# ESP32_schematic1.net
KiCad netlist of a schematic drawn in Altium Designer
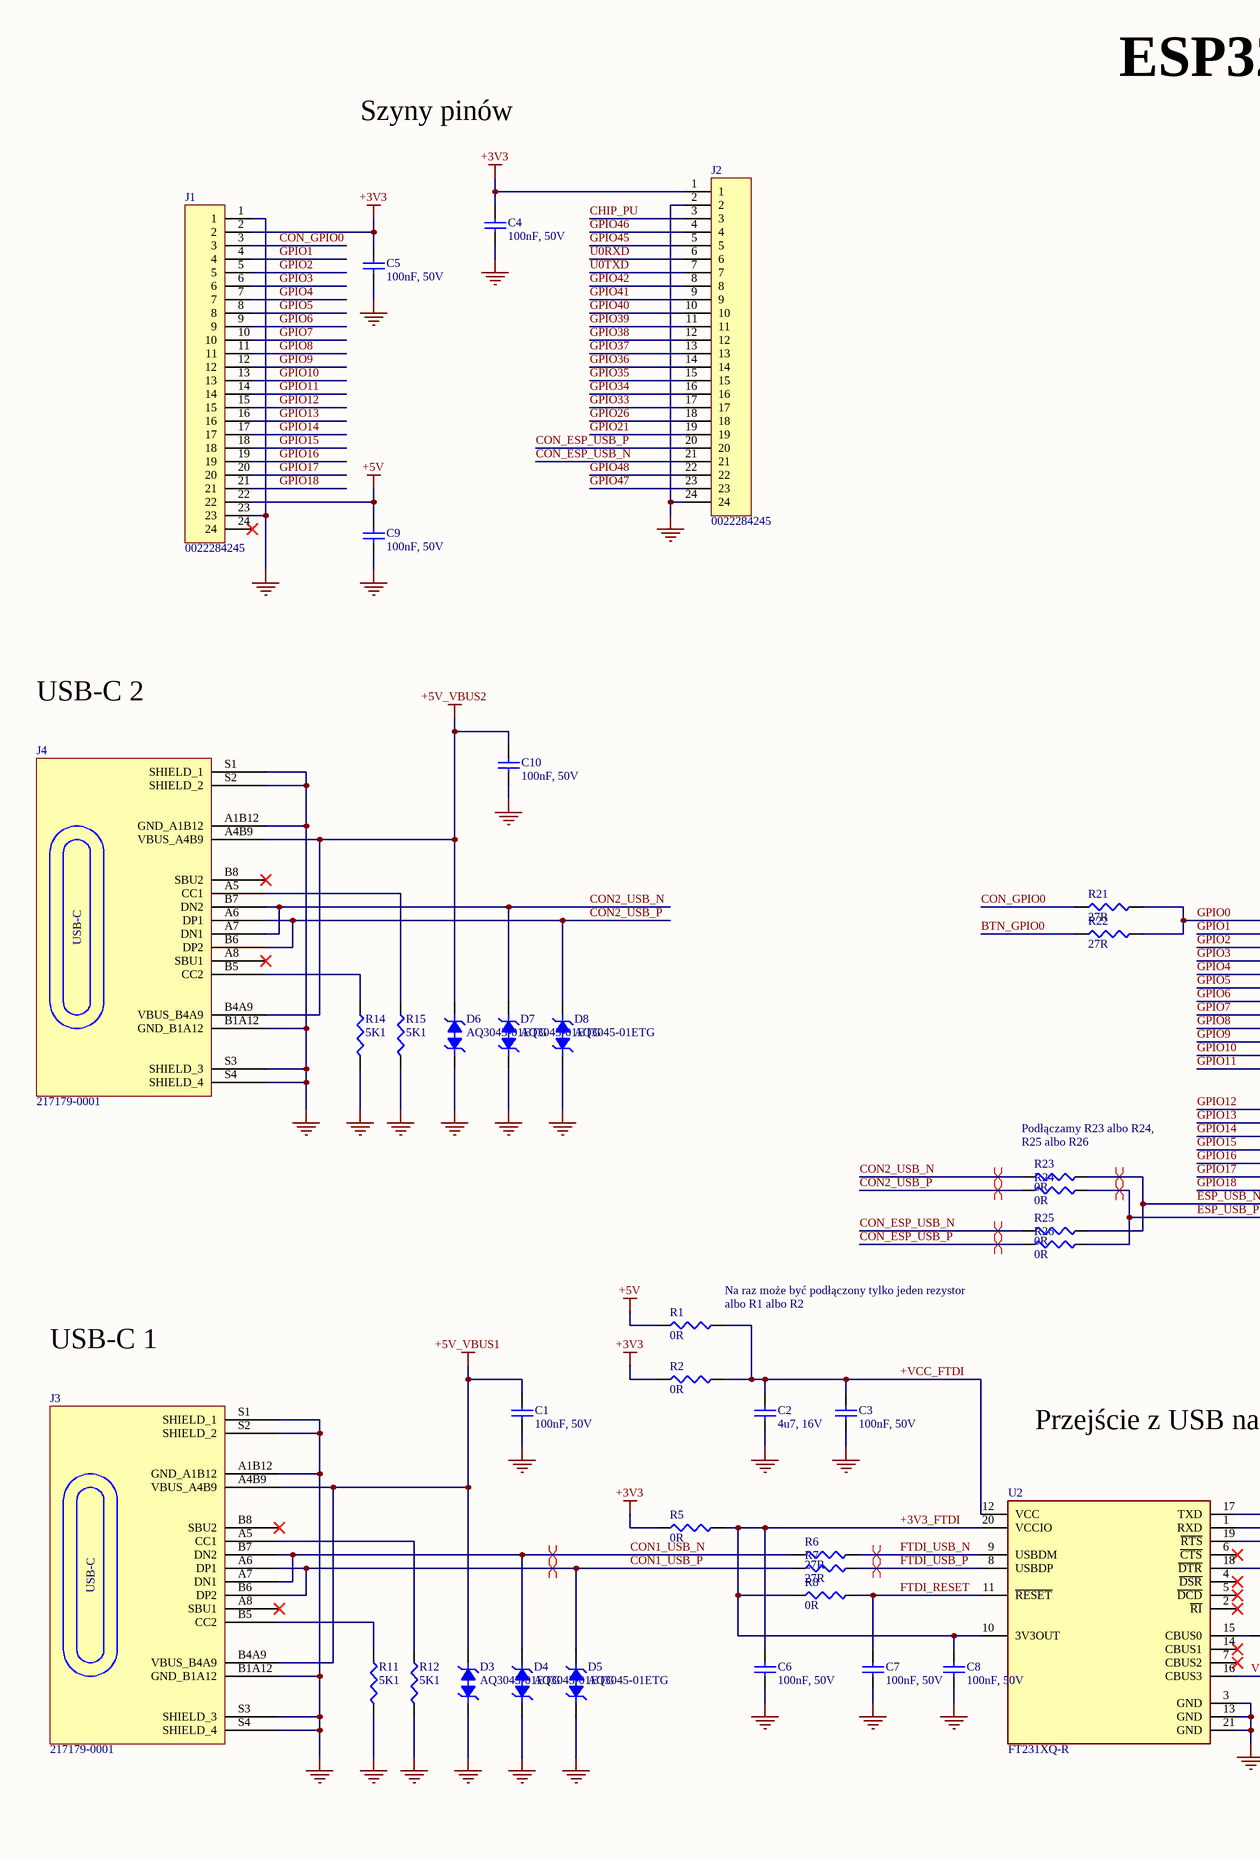
[diagram p0: ESP32_schematic1.SchDoc, left]
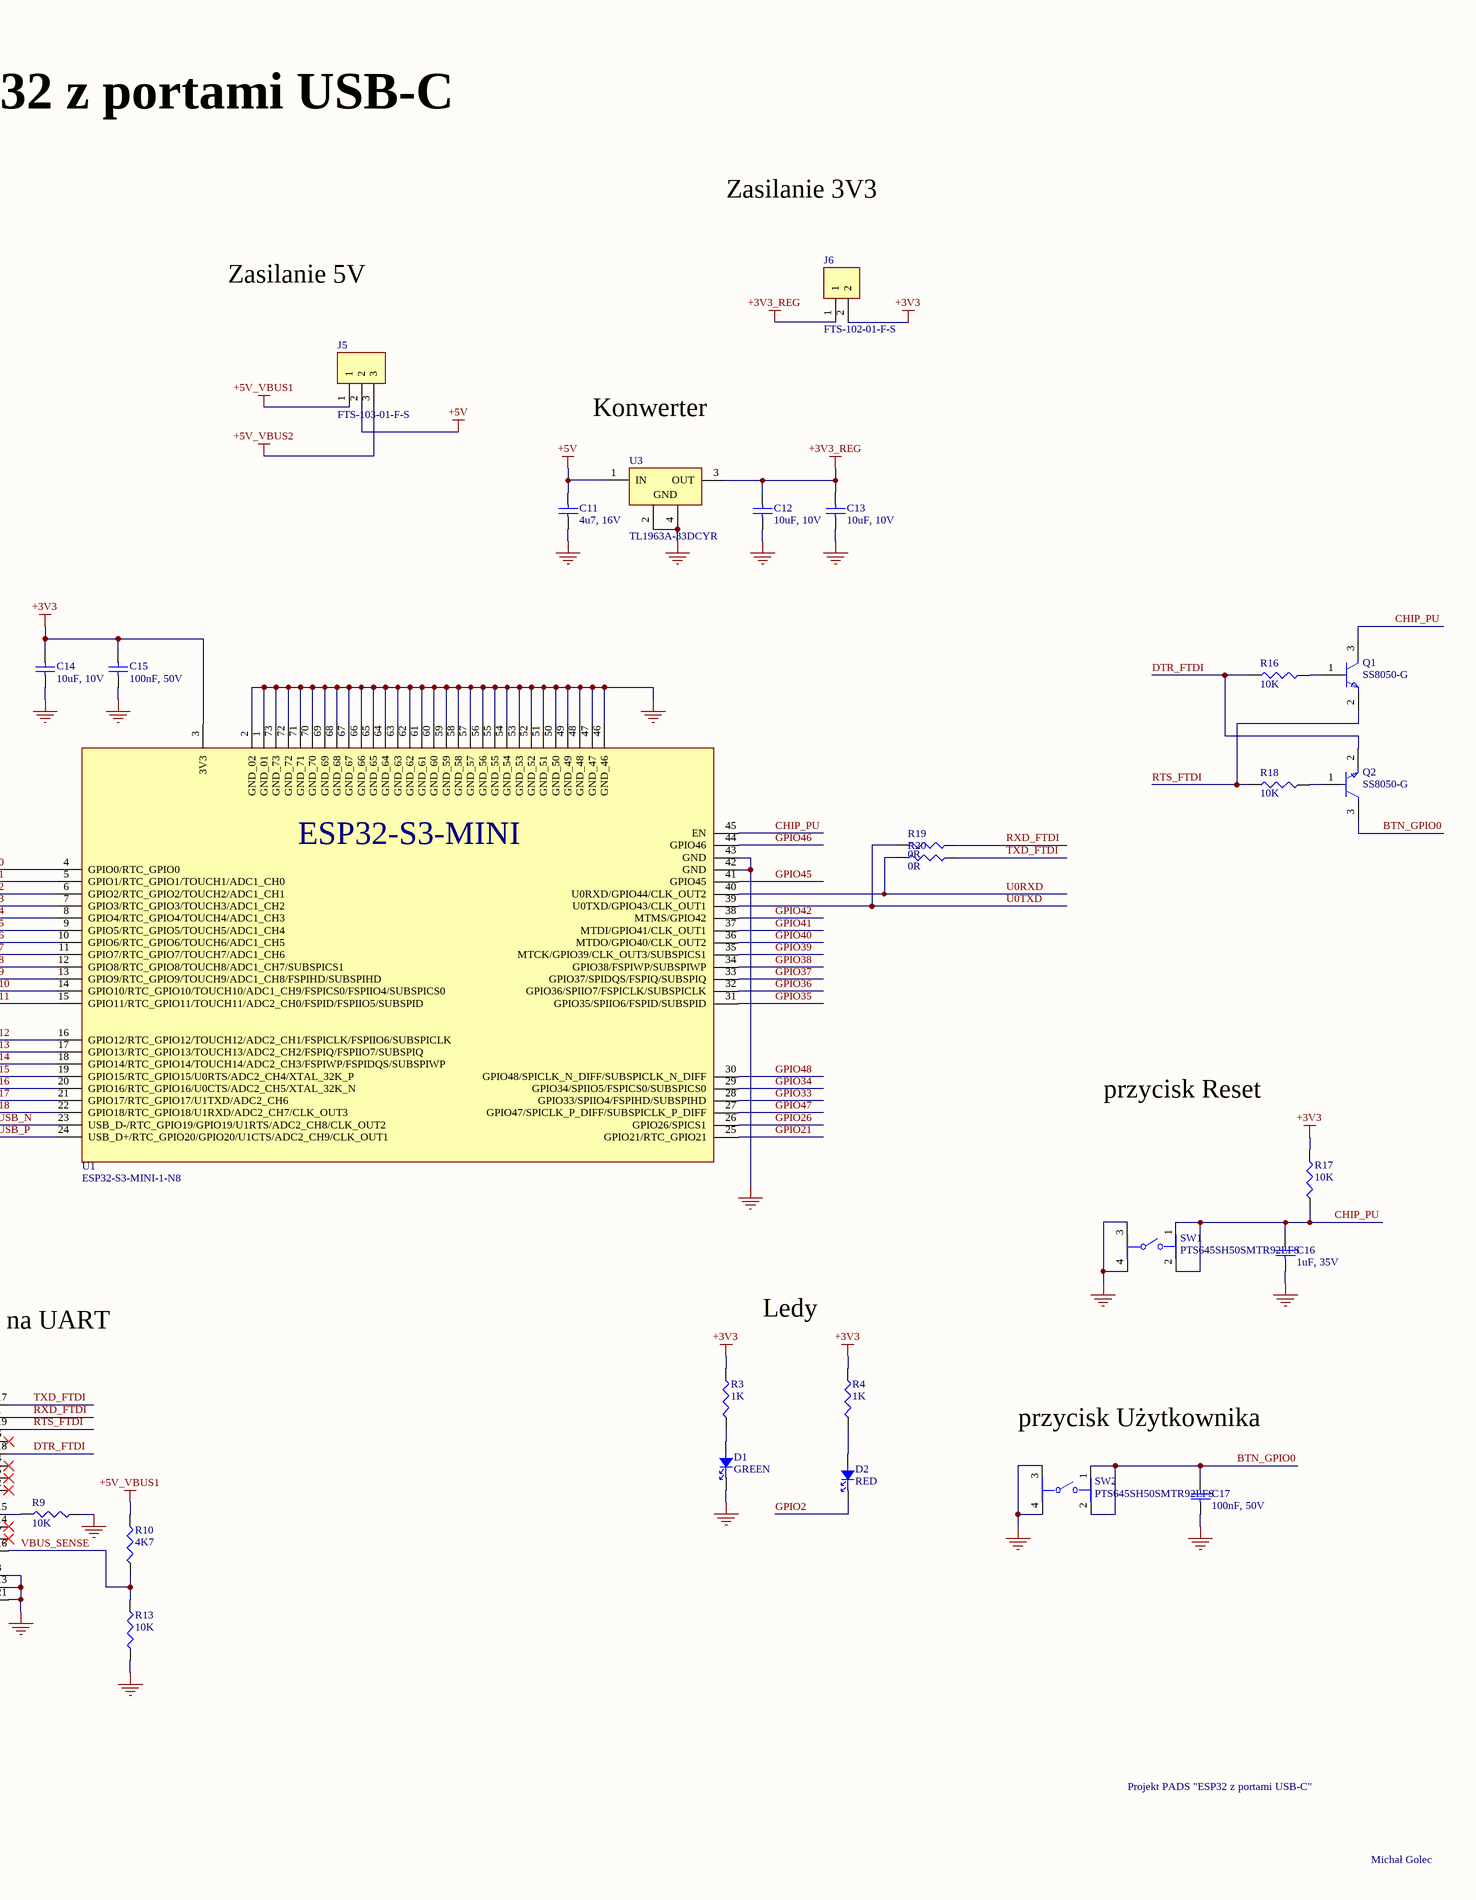
[diagram p1: ESP32_schematic1.SchDoc, right]

(export (version "E")
  (design (tool "Eeschema 10.0.6"))
  (components
    (comp (ref "C1")
      (value "100nF, 50V")
      (footprint "CAPC1005X55N")
      (description "CAP CER 0.1UF 50V X7R 0402")
      (fields
        (field (name "MANUFACTURER") "Samsung")
        (field (name "MANUFACTURER PART NUMBER") "CL05B104KB54PNC")
      )
      (libsource (lib "Schlib") (part "CL05B104KB54PNC"))
    )
    (comp (ref "C2")
      (value "4u7, 16V")
      (footprint "CAPC1005X55N")
      (description "CAP CER 4.7UF 16V X5R 0402")
      (fields
        (field (name "MANUFACTURER") "Samsung")
        (field (name "MANUFACTURER PART NUMBER") "CL05A475MO5NUNC")
      )
      (libsource (lib "Schlib") (part "CL05A475MO5NUNC"))
    )
    (comp (ref "C3")
      (value "100nF, 50V")
      (footprint "CAPC1005X55N")
      (description "CAP CER 0.1UF 50V X7R 0402")
      (fields
        (field (name "MANUFACTURER") "Samsung")
        (field (name "MANUFACTURER PART NUMBER") "CL05B104KB54PNC")
      )
      (libsource (lib "Schlib") (part "CL05B104KB54PNC"))
    )
    (comp (ref "C4")
      (value "100nF, 50V")
      (footprint "CAPC1005X55N")
      (description "CAP CER 0.1UF 50V X7R 0402")
      (fields
        (field (name "MANUFACTURER") "Samsung")
        (field (name "MANUFACTURER PART NUMBER") "CL05B104KB54PNC")
      )
      (libsource (lib "Schlib") (part "CL05B104KB54PNC"))
    )
    (comp (ref "C5")
      (value "100nF, 50V")
      (footprint "CAPC1005X55N")
      (description "CAP CER 0.1UF 50V X7R 0402")
      (fields
        (field (name "MANUFACTURER") "Samsung")
        (field (name "MANUFACTURER PART NUMBER") "CL05B104KB54PNC")
      )
      (libsource (lib "Schlib") (part "CL05B104KB54PNC"))
    )
    (comp (ref "C6")
      (value "100nF, 50V")
      (footprint "CAPC1005X55N")
      (description "CAP CER 0.1UF 50V X7R 0402")
      (fields
        (field (name "MANUFACTURER") "Samsung")
        (field (name "MANUFACTURER PART NUMBER") "CL05B104KB54PNC")
      )
      (libsource (lib "Schlib") (part "CL05B104KB54PNC"))
    )
    (comp (ref "C7")
      (value "100nF, 50V")
      (footprint "CAPC1005X55N")
      (description "CAP CER 0.1UF 50V X7R 0402")
      (fields
        (field (name "MANUFACTURER") "Samsung")
        (field (name "MANUFACTURER PART NUMBER") "CL05B104KB54PNC")
      )
      (libsource (lib "Schlib") (part "CL05B104KB54PNC"))
    )
    (comp (ref "C8")
      (value "100nF, 50V")
      (footprint "CAPC1005X55N")
      (description "CAP CER 0.1UF 50V X7R 0402")
      (fields
        (field (name "MANUFACTURER") "Samsung")
        (field (name "MANUFACTURER PART NUMBER") "CL05B104KB54PNC")
      )
      (libsource (lib "Schlib") (part "CL05B104KB54PNC"))
    )
    (comp (ref "C9")
      (value "100nF, 50V")
      (footprint "CAPC1005X55N")
      (description "CAP CER 0.1UF 50V X7R 0402")
      (fields
        (field (name "MANUFACTURER") "Samsung")
        (field (name "MANUFACTURER PART NUMBER") "CL05B104KB54PNC")
      )
      (libsource (lib "Schlib") (part "CL05B104KB54PNC"))
    )
    (comp (ref "C10")
      (value "100nF, 50V")
      (footprint "CAPC1005X55N")
      (description "CAP CER 0.1UF 50V X7R 0402")
      (fields
        (field (name "MANUFACTURER") "Samsung")
        (field (name "MANUFACTURER PART NUMBER") "CL05B104KB54PNC")
      )
      (libsource (lib "Schlib") (part "CL05B104KB54PNC"))
    )
    (comp (ref "C11")
      (value "4u7, 16V")
      (footprint "CAPC1005X55N")
      (description "CAP CER 4.7UF 16V X5R 0402")
      (fields
        (field (name "MANUFACTURER") "Samsung")
        (field (name "MANUFACTURER PART NUMBER") "CL05A475MO5NUNC")
      )
      (libsource (lib "Schlib") (part "CL05A475MO5NUNC"))
    )
    (comp (ref "C12")
      (value "10uF, 10V")
      (footprint "CAPC1005X55N")
      (description "CAP CER 10UF 10V X5R 0402")
      (fields
        (field (name "MANUFACTURER") "Samsung")
        (field (name "MANUFACTURER PART NUMBER") "CL05A106MP8NUB8")
      )
      (libsource (lib "Schlib") (part "CL05A106MP8NUB8"))
    )
    (comp (ref "C13")
      (value "10uF, 10V")
      (footprint "CAPC1005X55N")
      (description "CAP CER 10UF 10V X5R 0402")
      (fields
        (field (name "MANUFACTURER") "Samsung")
        (field (name "MANUFACTURER PART NUMBER") "CL05A106MP8NUB8")
      )
      (libsource (lib "Schlib") (part "CL05A106MP8NUB8"))
    )
    (comp (ref "C14")
      (value "10uF, 10V")
      (footprint "CAPC1005X55N")
      (description "CAP CER 10UF 10V X5R 0402")
      (fields
        (field (name "MANUFACTURER") "Samsung")
        (field (name "MANUFACTURER PART NUMBER") "CL05A106MP8NUB8")
      )
      (libsource (lib "Schlib") (part "CL05A106MP8NUB8"))
    )
    (comp (ref "C15")
      (value "100nF, 50V")
      (footprint "CAPC1005X55N")
      (description "CAP CER 0.1UF 50V X7R 0402")
      (fields
        (field (name "MANUFACTURER") "Samsung")
        (field (name "MANUFACTURER PART NUMBER") "CL05B104KB54PNC")
      )
      (libsource (lib "Schlib") (part "CL05B104KB54PNC"))
    )
    (comp (ref "C16")
      (value "1uF, 35V")
      (footprint "CAPC1005X55N")
      (description "CAP CER 1UF 35V X5R 0402")
      (fields
        (field (name "MANUFACTURER") "Samsung")
        (field (name "MANUFACTURER PART NUMBER") "CL05A105KL5NRNC")
      )
      (libsource (lib "Schlib") (part "CL05A105KL5NRNC"))
    )
    (comp (ref "C17")
      (value "100nF, 50V")
      (footprint "CAPC1005X55N")
      (description "CAP CER 0.1UF 50V X7R 0402")
      (fields
        (field (name "MANUFACTURER") "Samsung")
        (field (name "MANUFACTURER PART NUMBER") "CL05B104KB54PNC")
      )
      (libsource (lib "Schlib") (part "CL05B104KB54PNC"))
    )
    (comp (ref "D1")
      (value "GREEN")
      (footprint "LED0402G")
      (description "LED YLW-GRN 0402 SMD")
      (fields
        (field (name "MANUFACTURER") "Vishay")
        (field (name "MANUFACTURER PART NUMBER") "VLMG1500-GS08")
      )
      (libsource (lib "Schlib") (part "VLMG1500-GS08"))
    )
    (comp (ref "D2")
      (value "RED")
      (footprint "LED0402R")
      (description "LED RED 0402 SMD")
      (fields
        (field (name "MANUFACTURER") "Vishay")
        (field (name "MANUFACTURER PART NUMBER") "VLMS1500-GS08")
      )
      (libsource (lib "Schlib") (part "VLMS1500-GS08"))
    )
    (comp (ref "D3")
      (value "AQ3045-01ETG")
      (footprint "SOD882")
      (description "TVS DIODE 5.3VWM 12VC SOD882")
      (fields (field (name "MANUFACTURER") "Littelfuse") (field (name "LCSC PART NUMBER") "C3710326"))
      (libsource (lib "Schlib") (part "AQ3045-01ETG"))
    )
    (comp (ref "D4")
      (value "AQ3045-01ETG")
      (footprint "SOD882")
      (description "TVS DIODE 5.3VWM 12VC SOD882")
      (fields (field (name "MANUFACTURER") "Littelfuse") (field (name "LCSC PART NUMBER") "C3710326"))
      (libsource (lib "Schlib") (part "AQ3045-01ETG"))
    )
    (comp (ref "D5")
      (value "AQ3045-01ETG")
      (footprint "SOD882")
      (description "TVS DIODE 5.3VWM 12VC SOD882")
      (fields (field (name "MANUFACTURER") "Littelfuse") (field (name "LCSC PART NUMBER") "C3710326"))
      (libsource (lib "Schlib") (part "AQ3045-01ETG"))
    )
    (comp (ref "D6")
      (value "AQ3045-01ETG")
      (footprint "SOD882")
      (description "TVS DIODE 5.3VWM 12VC SOD882")
      (fields (field (name "MANUFACTURER") "Littelfuse") (field (name "LCSC PART NUMBER") "C3710326"))
      (libsource (lib "Schlib") (part "AQ3045-01ETG"))
    )
    (comp (ref "D7")
      (value "AQ3045-01ETG")
      (footprint "SOD882")
      (description "TVS DIODE 5.3VWM 12VC SOD882")
      (fields (field (name "MANUFACTURER") "Littelfuse") (field (name "LCSC PART NUMBER") "C3710326"))
      (libsource (lib "Schlib") (part "AQ3045-01ETG"))
    )
    (comp (ref "D8")
      (value "AQ3045-01ETG")
      (footprint "SOD882")
      (description "TVS DIODE 5.3VWM 12VC SOD882")
      (fields (field (name "MANUFACTURER") "Littelfuse") (field (name "LCSC PART NUMBER") "C3710326"))
      (libsource (lib "Schlib") (part "AQ3045-01ETG"))
    )
    (comp (ref "J1")
      (value "0022284245")
      (footprint "HDR_1X24_2.54MM")
      (description "CONN HEADER VERT 24POS 2.54MM")
      (fields (field (name "MANUFACTURER") "Molex") (field (name "LCSC PART NUMBER") "C7145888"))
      (libsource (lib "") (part "0022284245_1"))
    )
    (comp (ref "J2")
      (value "0022284245")
      (footprint "HDR_1X24_2.54MM")
      (description "CONN HEADER VERT 24POS 2.54MM")
      (fields (field (name "MANUFACTURER") "Molex") (field (name "LCSC PART NUMBER") "C7145888"))
      (libsource (lib "Schlib") (part "0022284245"))
    )
    (comp (ref "J3")
      (value "217179-0001")
      (footprint "FP-2171790001-MFG")
      (description "CONN RCP USB2.0 TYP C 24P SMD RA")
      (fields (field (name "MANUFACTURER") "Molex") (field (name "LCSC PART NUMBER") "C3197684"))
      (libsource (lib "Schlib") (part "217179-0001"))
    )
    (comp (ref "J4")
      (value "217179-0001")
      (footprint "FP-2171790001-MFG")
      (description "CONN RCP USB2.0 TYP C 24P SMD RA")
      (fields (field (name "MANUFACTURER") "Molex") (field (name "LCSC PART NUMBER") "C3197684"))
      (libsource (lib "Schlib") (part "217179-0001"))
    )
    (comp (ref "J5")
      (value "FTS-103-01-F-S")
      (footprint "HDR_1X3_1.27MM")
      (description "CONN HEADER VERT 3POS 1.27MM")
      (fields (field (name "MANUFACTURER") "Samtec") (field (name "LCSC PART NUMBER") "C3333578"))
      (libsource (lib "Schlib") (part "FTS-103-01-F-S"))
    )
    (comp (ref "J6")
      (value "FTS-102-01-F-S")
      (footprint "HDR_1X2_1.27MM")
      (description "CONN HEADER VERT 2POS 1.27MM")
      (fields (field (name "MANUFACTURER") "Samtec") (field (name "LCSC PART NUMBER") "C6045317"))
      (libsource (lib "Schlib") (part "FTS-102-01-F-S"))
    )
    (comp (ref "Q1")
      (value "SS8050-G")
      (footprint "FP-SS8050-G-IPC_B")
      (description "TRANS NPN 25V 1.5A SOT23-3")
      (fields (field (name "MANUFACTURER") "Comchip") (field (name "LCSC PART NUMBER") "C164886"))
      (libsource (lib "Schlib") (part "SS8050-G"))
    )
    (comp (ref "Q2")
      (value "SS8050-G")
      (footprint "FP-SS8050-G-IPC_B")
      (description "TRANS NPN 25V 1.5A SOT23-3")
      (fields (field (name "MANUFACTURER") "Comchip") (field (name "LCSC PART NUMBER") "C164886"))
      (libsource (lib "Schlib") (part "SS8050-G"))
    )
    (comp (ref "R1")
      (value "0R")
      (footprint "RESC1005X37N")
      (description "RES 0 OHM JUMPER 1/16W 0402")
      (fields
        (field (name "MANUFACTURER") "Yageo")
        (field (name "MANUFACTURER PART NUMBER") "RC0402JR-070RL")
      )
      (libsource (lib "Schlib") (part "RC0402JR-070RL"))
    )
    (comp (ref "R2")
      (value "0R")
      (footprint "RESC1005X37N")
      (description "RES 0 OHM JUMPER 1/16W 0402")
      (fields
        (field (name "MANUFACTURER") "Yageo")
        (field (name "MANUFACTURER PART NUMBER") "RC0402JR-070RL")
      )
      (libsource (lib "Schlib") (part "RC0402JR-070RL"))
    )
    (comp (ref "R3")
      (value "1K")
      (footprint "RESC1005X37N")
      (description "RES 1K OHM 1% 1/16W 0402")
      (fields
        (field (name "MANUFACTURER") "Yageo")
        (field (name "MANUFACTURER PART NUMBER") "RC0402FR-071KL")
      )
      (libsource (lib "Schlib") (part "RC0402FR-071KL"))
    )
    (comp (ref "R4")
      (value "1K")
      (footprint "RESC1005X37N")
      (description "RES 1K OHM 1% 1/16W 0402")
      (fields
        (field (name "MANUFACTURER") "Yageo")
        (field (name "MANUFACTURER PART NUMBER") "RC0402FR-071KL")
      )
      (libsource (lib "Schlib") (part "RC0402FR-071KL"))
    )
    (comp (ref "R5")
      (value "0R")
      (footprint "RESC1005X37N")
      (description "RES 0 OHM JUMPER 1/16W 0402")
      (fields
        (field (name "MANUFACTURER") "Yageo")
        (field (name "MANUFACTURER PART NUMBER") "RC0402JR-070RL")
      )
      (libsource (lib "Schlib") (part "RC0402JR-070RL"))
    )
    (comp (ref "R6")
      (value "27R")
      (footprint "RESC1005X37N")
      (description "RES 27 OHM 1% 1/16W 0402")
      (fields
        (field (name "MANUFACTURER") "Yageo")
        (field (name "MANUFACTURER PART NUMBER") "RC0402FR-0727RL")
      )
      (libsource (lib "Schlib") (part "RC0402FR-0727RL"))
    )
    (comp (ref "R7")
      (value "27R")
      (footprint "RESC1005X37N")
      (description "RES 27 OHM 1% 1/16W 0402")
      (fields
        (field (name "MANUFACTURER") "Yageo")
        (field (name "MANUFACTURER PART NUMBER") "RC0402FR-0727RL")
      )
      (libsource (lib "Schlib") (part "RC0402FR-0727RL"))
    )
    (comp (ref "R8")
      (value "0R")
      (footprint "RESC1005X37N")
      (description "RES 0 OHM JUMPER 1/16W 0402")
      (fields
        (field (name "MANUFACTURER") "Yageo")
        (field (name "MANUFACTURER PART NUMBER") "RC0402JR-070RL")
      )
      (libsource (lib "Schlib") (part "RC0402JR-070RL"))
    )
    (comp (ref "R9")
      (value "10K")
      (footprint "RESC1005X37N")
      (description "RES SMD 10K OHM 1% 1/16W 0402")
      (fields
        (field (name "MANUFACTURER") "Yageo")
        (field (name "MANUFACTURER PART NUMBER") "AC0402FR-0710KL")
      )
      (libsource (lib "Schlib") (part "AC0402FR-0710KL"))
    )
    (comp (ref "R10")
      (value "4K7")
      (footprint "RESC1005X37N")
      (description "RES 4.7K OHM 1% 1/16W 0402")
      (fields
        (field (name "MANUFACTURER") "Yageo")
        (field (name "MANUFACTURER PART NUMBER") "RC0402FR-074K7L")
      )
      (libsource (lib "Schlib") (part "RC0402FR-074K7L"))
    )
    (comp (ref "R11")
      (value "5K1")
      (footprint "RESC1005X37N")
      (description "RES SMD 5.1K OHM 1% 1/16W 0402")
      (fields
        (field (name "MANUFACTURER") "Yageo")
        (field (name "MANUFACTURER PART NUMBER") "AC0402FR-075K1L")
      )
      (libsource (lib "Schlib") (part "AC0402FR-075K1L"))
    )
    (comp (ref "R12")
      (value "5K1")
      (footprint "RESC1005X37N")
      (description "RES SMD 5.1K OHM 1% 1/16W 0402")
      (fields
        (field (name "MANUFACTURER") "Yageo")
        (field (name "MANUFACTURER PART NUMBER") "AC0402FR-075K1L")
      )
      (libsource (lib "Schlib") (part "AC0402FR-075K1L"))
    )
    (comp (ref "R13")
      (value "10K")
      (footprint "RESC1005X37N")
      (description "RES SMD 10K OHM 1% 1/16W 0402")
      (fields
        (field (name "MANUFACTURER") "Yageo")
        (field (name "MANUFACTURER PART NUMBER") "AC0402FR-0710KL")
      )
      (libsource (lib "Schlib") (part "AC0402FR-0710KL"))
    )
    (comp (ref "R14")
      (value "5K1")
      (footprint "RESC1005X37N")
      (description "RES SMD 5.1K OHM 1% 1/16W 0402")
      (fields
        (field (name "MANUFACTURER") "Yageo")
        (field (name "MANUFACTURER PART NUMBER") "AC0402FR-075K1L")
      )
      (libsource (lib "Schlib") (part "AC0402FR-075K1L"))
    )
    (comp (ref "R15")
      (value "5K1")
      (footprint "RESC1005X37N")
      (description "RES SMD 5.1K OHM 1% 1/16W 0402")
      (fields
        (field (name "MANUFACTURER") "Yageo")
        (field (name "MANUFACTURER PART NUMBER") "AC0402FR-075K1L")
      )
      (libsource (lib "Schlib") (part "AC0402FR-075K1L"))
    )
    (comp (ref "R16")
      (value "10K")
      (footprint "RESC1005X37N")
      (description "RES SMD 10K OHM 1% 1/16W 0402")
      (fields
        (field (name "MANUFACTURER") "Yageo")
        (field (name "MANUFACTURER PART NUMBER") "AC0402FR-0710KL")
      )
      (libsource (lib "Schlib") (part "AC0402FR-0710KL"))
    )
    (comp (ref "R17")
      (value "10K")
      (footprint "RESC1005X37N")
      (description "RES SMD 10K OHM 1% 1/16W 0402")
      (fields
        (field (name "MANUFACTURER") "Yageo")
        (field (name "MANUFACTURER PART NUMBER") "AC0402FR-0710KL")
      )
      (libsource (lib "Schlib") (part "AC0402FR-0710KL"))
    )
    (comp (ref "R18")
      (value "10K")
      (footprint "RESC1005X37N")
      (description "RES SMD 10K OHM 1% 1/16W 0402")
      (fields
        (field (name "MANUFACTURER") "Yageo")
        (field (name "MANUFACTURER PART NUMBER") "AC0402FR-0710KL")
      )
      (libsource (lib "Schlib") (part "AC0402FR-0710KL"))
    )
    (comp (ref "R19")
      (value "0R")
      (footprint "RESC1005X37N")
      (description "RES 0 OHM JUMPER 1/16W 0402")
      (fields
        (field (name "MANUFACTURER") "Yageo")
        (field (name "MANUFACTURER PART NUMBER") "RC0402JR-070RL")
      )
      (libsource (lib "Schlib") (part "RC0402JR-070RL"))
    )
    (comp (ref "R20")
      (value "0R")
      (footprint "RESC1005X37N")
      (description "RES 0 OHM JUMPER 1/16W 0402")
      (fields
        (field (name "MANUFACTURER") "Yageo")
        (field (name "MANUFACTURER PART NUMBER") "RC0402JR-070RL")
      )
      (libsource (lib "Schlib") (part "RC0402JR-070RL"))
    )
    (comp (ref "R21")
      (value "27R")
      (footprint "RESC1005X37N")
      (description "RES 27 OHM 1% 1/16W 0402")
      (fields
        (field (name "MANUFACTURER") "Yageo")
        (field (name "MANUFACTURER PART NUMBER") "RC0402FR-0727RL")
      )
      (libsource (lib "Schlib") (part "RC0402FR-0727RL"))
    )
    (comp (ref "R22")
      (value "27R")
      (footprint "RESC1005X37N")
      (description "RES 27 OHM 1% 1/16W 0402")
      (fields
        (field (name "MANUFACTURER") "Yageo")
        (field (name "MANUFACTURER PART NUMBER") "RC0402FR-0727RL")
      )
      (libsource (lib "Schlib") (part "RC0402FR-0727RL"))
    )
    (comp (ref "R23")
      (value "0R")
      (footprint "RESC1005X37N")
      (description "RES 0 OHM JUMPER 1/16W 0402")
      (fields
        (field (name "MANUFACTURER") "Yageo")
        (field (name "MANUFACTURER PART NUMBER") "RC0402JR-070RL")
      )
      (libsource (lib "Schlib") (part "RC0402JR-070RL"))
    )
    (comp (ref "R24")
      (value "0R")
      (footprint "RESC1005X37N")
      (description "RES 0 OHM JUMPER 1/16W 0402")
      (fields
        (field (name "MANUFACTURER") "Yageo")
        (field (name "MANUFACTURER PART NUMBER") "RC0402JR-070RL")
      )
      (libsource (lib "Schlib") (part "RC0402JR-070RL"))
    )
    (comp (ref "R25")
      (value "0R")
      (footprint "RESC1005X37N")
      (description "RES 0 OHM JUMPER 1/16W 0402")
      (fields
        (field (name "MANUFACTURER") "Yageo")
        (field (name "MANUFACTURER PART NUMBER") "RC0402JR-070RL")
      )
      (libsource (lib "Schlib") (part "RC0402JR-070RL"))
    )
    (comp (ref "R26")
      (value "0R")
      (footprint "RESC1005X37N")
      (description "RES 0 OHM JUMPER 1/16W 0402")
      (fields
        (field (name "MANUFACTURER") "Yageo")
        (field (name "MANUFACTURER PART NUMBER") "RC0402JR-070RL")
      )
      (libsource (lib "Schlib") (part "RC0402JR-070RL"))
    )
    (comp (ref "SW1")
      (value "PTS645SH50SMTR92LFS")
      (footprint "FP-PTS645SH50SMTR92LFS-MFG")
      (description "SWITCH TACTILE SPST-NO 0.05A 12V")
      (fields (field (name "MANUFACTURER") "ITT C&K") (field (name "LCSC PART NUMBER") "C221869"))
      (libsource (lib "Schlib") (part "PTS645SH50SMTR92LFS"))
    )
    (comp (ref "SW2")
      (value "PTS645SH50SMTR92LFS")
      (footprint "FP-PTS645SH50SMTR92LFS-MFG")
      (description "SWITCH TACTILE SPST-NO 0.05A 12V")
      (fields (field (name "MANUFACTURER") "ITT C&K") (field (name "LCSC PART NUMBER") "C221869"))
      (libsource (lib "Schlib") (part "PTS645SH50SMTR92LFS"))
    )
    (comp (ref "U1")
      (value "ESP32-S3-MINI-1-N8")
      (footprint "XCVR_ESP32-S3-MINI-1-N8")
      (description "SMD Module, ESP32-S3FN8, 8 mb Sp")
      (fields (field (name "MANUFACTURER") "Espressif Systems") (field (name "LCSC PART NUMBER") "C2913206"))
      (libsource (lib "Schlib") (part "ESP32-S3-MINI-1-N8"))
    )
    (comp (ref "U2")
      (value "FT231XQ-R")
      (footprint "FP-QFN-20-IPC_B")
      (description "IC USB SERIAL FULL UART 20QFN")
      (fields (field (name "MANUFACTURER") "FTDI") (field (name "LCSC PART NUMBER") "C132159"))
      (libsource (lib "Schlib") (part "FT231XQ-R"))
    )
    (comp (ref "U3")
      (value "TL1963A-33DCYR")
      (footprint "DCY0004A_N")
      (description "IC REG LINEAR 3.3V 1.5A SOT223-4")
      (fields (field (name "MANUFACTURER") "Texas Instruments") (field (name "LCSC PART NUMBER") "C181262"))
      (libsource (lib "Schlib") (part "TL1963A-33DCYR"))
    )
  )
  (nets
    (net (code "1") (name "+3V3") (class "Default")
      (node (ref "C14") (pin "2") (pinfunction "2_2") (pintype "passive"))
      (node (ref "C15") (pin "2") (pinfunction "2_2") (pintype "passive"))
      (node (ref "C4") (pin "2") (pinfunction "2_2") (pintype "passive"))
      (node (ref "C5") (pin "2") (pinfunction "2_2") (pintype "passive"))
      (node (ref "J1") (pin "2") (pinfunction "2_2") (pintype "passive"))
      (node (ref "J2") (pin "1") (pinfunction "1_1") (pintype "passive"))
      (node (ref "J6") (pin "2") (pinfunction "2_2") (pintype "passive"))
      (node (ref "R17") (pin "2") (pinfunction "2_2") (pintype "passive"))
      (node (ref "R2") (pin "1") (pinfunction "1_1") (pintype "passive"))
      (node (ref "R3") (pin "2") (pinfunction "2_2") (pintype "passive"))
      (node (ref "R4") (pin "2") (pinfunction "2_2") (pintype "passive"))
      (node (ref "R5") (pin "1") (pinfunction "1_1") (pintype "passive"))
      (node (ref "U1") (pin "3") (pinfunction "3V3_3") (pintype "passive"))
    )
    (net (code "2") (name "+3V3_REG") (class "Default")
      (node (ref "C12") (pin "2") (pinfunction "2_2") (pintype "passive"))
      (node (ref "C13") (pin "2") (pinfunction "2_2") (pintype "passive"))
      (node (ref "J6") (pin "1") (pinfunction "1_1") (pintype "passive"))
      (node (ref "U3") (pin "3") (pinfunction "OUT_3") (pintype "power_in"))
    )
    (net (code "3") (name "+5V") (class "Default")
      (node (ref "C11") (pin "2") (pinfunction "2_2") (pintype "passive"))
      (node (ref "C9") (pin "2") (pinfunction "2_2") (pintype "passive"))
      (node (ref "J1") (pin "22") (pinfunction "22_22") (pintype "passive"))
      (node (ref "J5") (pin "2") (pinfunction "2_2") (pintype "passive"))
      (node (ref "R1") (pin "1") (pinfunction "1_1") (pintype "passive"))
      (node (ref "U3") (pin "1") (pinfunction "IN_1") (pintype "power_in"))
    )
    (net (code "4") (name "+5V_VBUS1") (class "Default")
      (node (ref "C1") (pin "2") (pinfunction "2_2") (pintype "passive"))
      (node (ref "D3") (pin "2") (pinfunction "2_2") (pintype "passive"))
      (node (ref "J3") (pin "A4B9") (pinfunction "VBUS_A4B9_A4B9") (pintype "passive"))
      (node (ref "J3") (pin "B4A9") (pinfunction "VBUS_B4A9_B4A9") (pintype "passive"))
      (node (ref "J5") (pin "1") (pinfunction "1_1") (pintype "passive"))
      (node (ref "R10") (pin "2") (pinfunction "2_2") (pintype "passive"))
    )
    (net (code "5") (name "+5V_VBUS2") (class "Default")
      (node (ref "C10") (pin "2") (pinfunction "2_2") (pintype "passive"))
      (node (ref "D6") (pin "2") (pinfunction "2_2") (pintype "passive"))
      (node (ref "J4") (pin "A4B9") (pinfunction "VBUS_A4B9_A4B9") (pintype "passive"))
      (node (ref "J4") (pin "B4A9") (pinfunction "VBUS_B4A9_B4A9") (pintype "passive"))
      (node (ref "J5") (pin "3") (pinfunction "3_3") (pintype "passive"))
    )
    (net (code "6") (name "/+3V3_FTDI") (class "Default")
      (node (ref "C6") (pin "2") (pinfunction "2_2") (pintype "passive"))
      (node (ref "C8") (pin "2") (pinfunction "2_2") (pintype "passive"))
      (node (ref "R5") (pin "2") (pinfunction "2_2") (pintype "passive"))
      (node (ref "R8") (pin "1") (pinfunction "1_1") (pintype "passive"))
      (node (ref "U2") (pin "10") (pinfunction "3V3OUT_10") (pintype "passive"))
      (node (ref "U2") (pin "20") (pinfunction "VCCIO_20") (pintype "passive"))
    )
    (net (code "7") (name "/+VCC_FTDI") (class "Default")
      (node (ref "C2") (pin "2") (pinfunction "2_2") (pintype "passive"))
      (node (ref "C3") (pin "2") (pinfunction "2_2") (pintype "passive"))
      (node (ref "R1") (pin "2") (pinfunction "2_2") (pintype "passive"))
      (node (ref "R2") (pin "2") (pinfunction "2_2") (pintype "passive"))
      (node (ref "U2") (pin "12") (pinfunction "VCC_12") (pintype "passive"))
    )
    (net (code "8") (name "/BTN_GPIO0") (class "Default")
      (node (ref "C17") (pin "2") (pinfunction "2_2") (pintype "passive"))
      (node (ref "Q2") (pin "3") (pinfunction "C_3") (pintype "passive"))
      (node (ref "R22") (pin "1") (pinfunction "1_1") (pintype "passive"))
      (node (ref "SW2") (pin "1") (pinfunction "1_1") (pintype "passive"))
      (node (ref "SW2") (pin "2") (pinfunction "2_2") (pintype "passive"))
    )
    (net (code "9") (name "/CHIP_PU") (class "Default")
      (node (ref "C16") (pin "2") (pinfunction "2_2") (pintype "passive"))
      (node (ref "J2") (pin "3") (pinfunction "3_3") (pintype "passive"))
      (node (ref "Q1") (pin "3") (pinfunction "C_3") (pintype "passive"))
      (node (ref "R17") (pin "1") (pinfunction "1_1") (pintype "passive"))
      (node (ref "SW1") (pin "1") (pinfunction "1_1") (pintype "passive"))
      (node (ref "SW1") (pin "2") (pinfunction "2_2") (pintype "passive"))
      (node (ref "U1") (pin "45") (pinfunction "EN_45") (pintype "passive"))
    )
    (net (code "10") (name "/CON1_USB_N") (class "Default")
      (node (ref "D4") (pin "2") (pinfunction "2_2") (pintype "passive"))
      (node (ref "J3") (pin "A7") (pinfunction "DN1_A7") (pintype "passive"))
      (node (ref "J3") (pin "B7") (pinfunction "DN2_B7") (pintype "passive"))
      (node (ref "R6") (pin "1") (pinfunction "1_1") (pintype "passive"))
    )
    (net (code "11") (name "/CON1_USB_P") (class "Default")
      (node (ref "D5") (pin "2") (pinfunction "2_2") (pintype "passive"))
      (node (ref "J3") (pin "A6") (pinfunction "DP1_A6") (pintype "passive"))
      (node (ref "J3") (pin "B6") (pinfunction "DP2_B6") (pintype "passive"))
      (node (ref "R7") (pin "1") (pinfunction "1_1") (pintype "passive"))
    )
    (net (code "12") (name "/CON2_USB_N") (class "Default")
      (node (ref "D7") (pin "2") (pinfunction "2_2") (pintype "passive"))
      (node (ref "J4") (pin "A7") (pinfunction "DN1_A7") (pintype "passive"))
      (node (ref "J4") (pin "B7") (pinfunction "DN2_B7") (pintype "passive"))
      (node (ref "R23") (pin "1") (pinfunction "1_1") (pintype "passive"))
    )
    (net (code "13") (name "/CON2_USB_P") (class "Default")
      (node (ref "D8") (pin "2") (pinfunction "2_2") (pintype "passive"))
      (node (ref "J4") (pin "A6") (pinfunction "DP1_A6") (pintype "passive"))
      (node (ref "J4") (pin "B6") (pinfunction "DP2_B6") (pintype "passive"))
      (node (ref "R24") (pin "1") (pinfunction "1_1") (pintype "passive"))
    )
    (net (code "14") (name "/CON_ESP_USB_N") (class "Default")
      (node (ref "J2") (pin "21") (pinfunction "21_21") (pintype "passive"))
      (node (ref "R25") (pin "1") (pinfunction "1_1") (pintype "passive"))
    )
    (net (code "15") (name "/CON_ESP_USB_P") (class "Default")
      (node (ref "J2") (pin "20") (pinfunction "20_20") (pintype "passive"))
      (node (ref "R26") (pin "1") (pinfunction "1_1") (pintype "passive"))
    )
    (net (code "16") (name "/CON_GPIO0") (class "Default")
      (node (ref "J1") (pin "3") (pinfunction "3_3") (pintype "passive"))
      (node (ref "R21") (pin "1") (pinfunction "1_1") (pintype "passive"))
    )
    (net (code "17") (name "/DTR_FTDI") (class "Default")
      (node (ref "Q2") (pin "2") (pinfunction "E_2") (pintype "passive"))
      (node (ref "R16") (pin "1") (pinfunction "1_1") (pintype "passive"))
      (node (ref "U2") (pin "18") (pinfunction "~{DTR}_18") (pintype "passive"))
    )
    (net (code "18") (name "/ESP_USB_N") (class "Default")
      (node (ref "R23") (pin "2") (pinfunction "2_2") (pintype "passive"))
      (node (ref "R25") (pin "2") (pinfunction "2_2") (pintype "passive"))
      (node (ref "U1") (pin "23") (pinfunction "USB_D-/RTC_GPIO19/GPIO19/U1RTS/ADC2_CH8/CLK_OUT2_23") (pintype "passive"))
    )
    (net (code "19") (name "/ESP_USB_P") (class "Default")
      (node (ref "R24") (pin "2") (pinfunction "2_2") (pintype "passive"))
      (node (ref "R26") (pin "2") (pinfunction "2_2") (pintype "passive"))
      (node (ref "U1") (pin "24") (pinfunction "USB_D+/RTC_GPIO20/GPIO20/U1CTS/ADC2_CH9/CLK_OUT1_24") (pintype "passive"))
    )
    (net (code "20") (name "/FTDI_RESET") (class "Default")
      (node (ref "C7") (pin "2") (pinfunction "2_2") (pintype "passive"))
      (node (ref "R8") (pin "2") (pinfunction "2_2") (pintype "passive"))
      (node (ref "U2") (pin "11") (pinfunction "~{RESET}_11") (pintype "passive"))
    )
    (net (code "21") (name "/FTDI_USB_N") (class "Default")
      (node (ref "R6") (pin "2") (pinfunction "2_2") (pintype "passive"))
      (node (ref "U2") (pin "9") (pinfunction "USBDM_9") (pintype "passive"))
    )
    (net (code "22") (name "/FTDI_USB_P") (class "Default")
      (node (ref "R7") (pin "2") (pinfunction "2_2") (pintype "passive"))
      (node (ref "U2") (pin "8") (pinfunction "USBDP_8") (pintype "passive"))
    )
    (net (code "23") (name "/GPIO0") (class "Default")
      (node (ref "R21") (pin "2") (pinfunction "2_2") (pintype "passive"))
      (node (ref "R22") (pin "2") (pinfunction "2_2") (pintype "passive"))
      (node (ref "U1") (pin "4") (pinfunction "GPIO0/RTC_GPIO0_4") (pintype "passive"))
    )
    (net (code "24") (name "/GPIO1") (class "Default")
      (node (ref "J1") (pin "4") (pinfunction "4_4") (pintype "passive"))
      (node (ref "U1") (pin "5") (pinfunction "GPIO1/RTC_GPIO1/TOUCH1/ADC1_CH0_5") (pintype "passive"))
    )
    (net (code "25") (name "/GPIO2") (class "Default")
      (node (ref "D2") (pin "1") (pinfunction "1_1") (pintype "passive"))
      (node (ref "J1") (pin "5") (pinfunction "5_5") (pintype "passive"))
      (node (ref "U1") (pin "6") (pinfunction "GPIO2/RTC_GPIO2/TOUCH2/ADC1_CH1_6") (pintype "passive"))
    )
    (net (code "26") (name "/GPIO3") (class "Default")
      (node (ref "J1") (pin "6") (pinfunction "6_6") (pintype "passive"))
      (node (ref "U1") (pin "7") (pinfunction "GPIO3/RTC_GPIO3/TOUCH3/ADC1_CH2_7") (pintype "passive"))
    )
    (net (code "27") (name "/GPIO4") (class "Default")
      (node (ref "J1") (pin "7") (pinfunction "7_7") (pintype "passive"))
      (node (ref "U1") (pin "8") (pinfunction "GPIO4/RTC_GPIO4/TOUCH4/ADC1_CH3_8") (pintype "passive"))
    )
    (net (code "28") (name "/GPIO5") (class "Default")
      (node (ref "J1") (pin "8") (pinfunction "8_8") (pintype "passive"))
      (node (ref "U1") (pin "9") (pinfunction "GPIO5/RTC_GPIO5/TOUCH5/ADC1_CH4_9") (pintype "passive"))
    )
    (net (code "29") (name "/GPIO6") (class "Default")
      (node (ref "J1") (pin "9") (pinfunction "9_9") (pintype "passive"))
      (node (ref "U1") (pin "10") (pinfunction "GPIO6/RTC_GPIO6/TOUCH6/ADC1_CH5_10") (pintype "passive"))
    )
    (net (code "30") (name "/GPIO7") (class "Default")
      (node (ref "J1") (pin "10") (pinfunction "10_10") (pintype "passive"))
      (node (ref "U1") (pin "11") (pinfunction "GPIO7/RTC_GPIO7/TOUCH7/ADC1_CH6_11") (pintype "passive"))
    )
    (net (code "31") (name "/GPIO8") (class "Default")
      (node (ref "J1") (pin "11") (pinfunction "11_11") (pintype "passive"))
      (node (ref "U1") (pin "12") (pinfunction "GPIO8/RTC_GPIO8/TOUCH8/ADC1_CH7/SUBSPICS1_12") (pintype "passive"))
    )
    (net (code "32") (name "/GPIO9") (class "Default")
      (node (ref "J1") (pin "12") (pinfunction "12_12") (pintype "passive"))
      (node (ref "U1") (pin "13") (pinfunction "GPIO9/RTC_GPIO9/TOUCH9/ADC1_CH8/FSPIHD/SUBSPIHD_13") (pintype "passive"))
    )
    (net (code "33") (name "/GPIO10") (class "Default")
      (node (ref "J1") (pin "13") (pinfunction "13_13") (pintype "passive"))
      (node (ref "U1") (pin "14") (pinfunction "GPIO10/RTC_GPIO10/TOUCH10/ADC1_CH9/FSPICS0/FSPIIO4/SUBSPICS0_14") (pintype "passive"))
    )
    (net (code "34") (name "/GPIO11") (class "Default")
      (node (ref "J1") (pin "14") (pinfunction "14_14") (pintype "passive"))
      (node (ref "U1") (pin "15") (pinfunction "GPIO11/RTC_GPIO11/TOUCH11/ADC2_CH0/FSPID/FSPIIO5/SUBSPID_15") (pintype "passive"))
    )
    (net (code "35") (name "/GPIO12") (class "Default")
      (node (ref "J1") (pin "15") (pinfunction "15_15") (pintype "passive"))
      (node (ref "U1") (pin "16") (pinfunction "GPIO12/RTC_GPIO12/TOUCH12/ADC2_CH1/FSPICLK/FSPIIO6/SUBSPICLK_16") (pintype "passive"))
    )
    (net (code "36") (name "/GPIO13") (class "Default")
      (node (ref "J1") (pin "16") (pinfunction "16_16") (pintype "passive"))
      (node (ref "U1") (pin "17") (pinfunction "GPIO13/RTC_GPIO13/TOUCH13/ADC2_CH2/FSPIQ/FSPIIO7/SUBSPIQ_17") (pintype "passive"))
    )
    (net (code "37") (name "/GPIO14") (class "Default")
      (node (ref "J1") (pin "17") (pinfunction "17_17") (pintype "passive"))
      (node (ref "U1") (pin "18") (pinfunction "GPIO14/RTC_GPIO14/TOUCH14/ADC2_CH3/FSPIWP/FSPIDQS/SUBSPIWP_18") (pintype "passive"))
    )
    (net (code "38") (name "/GPIO15") (class "Default")
      (node (ref "J1") (pin "18") (pinfunction "18_18") (pintype "passive"))
      (node (ref "U1") (pin "19") (pinfunction "GPIO15/RTC_GPIO15/U0RTS/ADC2_CH4/XTAL_32K_P_19") (pintype "passive"))
    )
    (net (code "39") (name "/GPIO16") (class "Default")
      (node (ref "J1") (pin "19") (pinfunction "19_19") (pintype "passive"))
      (node (ref "U1") (pin "20") (pinfunction "GPIO16/RTC_GPIO16/U0CTS/ADC2_CH5/XTAL_32K_N_20") (pintype "passive"))
    )
    (net (code "40") (name "/GPIO17") (class "Default")
      (node (ref "J1") (pin "20") (pinfunction "20_20") (pintype "passive"))
      (node (ref "U1") (pin "21") (pinfunction "GPIO17/RTC_GPIO17/U1TXD/ADC2_CH6_21") (pintype "passive"))
    )
    (net (code "41") (name "/GPIO18") (class "Default")
      (node (ref "J1") (pin "21") (pinfunction "21_21") (pintype "passive"))
      (node (ref "U1") (pin "22") (pinfunction "GPIO18/RTC_GPIO18/U1RXD/ADC2_CH7/CLK_OUT3_22") (pintype "passive"))
    )
    (net (code "42") (name "/GPIO21") (class "Default")
      (node (ref "J2") (pin "19") (pinfunction "19_19") (pintype "passive"))
      (node (ref "U1") (pin "25") (pinfunction "GPIO21/RTC_GPIO21_25") (pintype "passive"))
    )
    (net (code "43") (name "/GPIO26") (class "Default")
      (node (ref "J2") (pin "18") (pinfunction "18_18") (pintype "passive"))
      (node (ref "U1") (pin "26") (pinfunction "GPIO26/SPICS1_26") (pintype "passive"))
    )
    (net (code "44") (name "/GPIO33") (class "Default")
      (node (ref "J2") (pin "17") (pinfunction "17_17") (pintype "passive"))
      (node (ref "U1") (pin "28") (pinfunction "GPIO33/SPIIO4/FSPIHD/SUBSPIHD_28") (pintype "passive"))
    )
    (net (code "45") (name "/GPIO34") (class "Default")
      (node (ref "J2") (pin "16") (pinfunction "16_16") (pintype "passive"))
      (node (ref "U1") (pin "29") (pinfunction "GPIO34/SPIIO5/FSPICS0/SUBSPICS0_29") (pintype "passive"))
    )
    (net (code "46") (name "/GPIO35") (class "Default")
      (node (ref "J2") (pin "15") (pinfunction "15_15") (pintype "passive"))
      (node (ref "U1") (pin "31") (pinfunction "GPIO35/SPIIO6/FSPID/SUBSPID_31") (pintype "passive"))
    )
    (net (code "47") (name "/GPIO36") (class "Default")
      (node (ref "J2") (pin "14") (pinfunction "14_14") (pintype "passive"))
      (node (ref "U1") (pin "32") (pinfunction "GPIO36/SPIIO7/FSPICLK/SUBSPICLK_32") (pintype "passive"))
    )
    (net (code "48") (name "/GPIO37") (class "Default")
      (node (ref "J2") (pin "13") (pinfunction "13_13") (pintype "passive"))
      (node (ref "U1") (pin "33") (pinfunction "GPIO37/SPIDQS/FSPIQ/SUBSPIQ_33") (pintype "passive"))
    )
    (net (code "49") (name "/GPIO38") (class "Default")
      (node (ref "J2") (pin "12") (pinfunction "12_12") (pintype "passive"))
      (node (ref "U1") (pin "34") (pinfunction "GPIO38/FSPIWP/SUBSPIWP_34") (pintype "passive"))
    )
    (net (code "50") (name "/GPIO39") (class "Default")
      (node (ref "J2") (pin "11") (pinfunction "11_11") (pintype "passive"))
      (node (ref "U1") (pin "35") (pinfunction "MTCK/GPIO39/CLK_OUT3/SUBSPICS1_35") (pintype "passive"))
    )
    (net (code "51") (name "/GPIO40") (class "Default")
      (node (ref "J2") (pin "10") (pinfunction "10_10") (pintype "passive"))
      (node (ref "U1") (pin "36") (pinfunction "MTDO/GPIO40/CLK_OUT2_36") (pintype "passive"))
    )
    (net (code "52") (name "/GPIO41") (class "Default")
      (node (ref "J2") (pin "9") (pinfunction "9_9") (pintype "passive"))
      (node (ref "U1") (pin "37") (pinfunction "MTDI/GPIO41/CLK_OUT1_37") (pintype "passive"))
    )
    (net (code "53") (name "/GPIO42") (class "Default")
      (node (ref "J2") (pin "8") (pinfunction "8_8") (pintype "passive"))
      (node (ref "U1") (pin "38") (pinfunction "MTMS/GPIO42_38") (pintype "passive"))
    )
    (net (code "54") (name "/GPIO45") (class "Default")
      (node (ref "J2") (pin "5") (pinfunction "5_5") (pintype "passive"))
      (node (ref "U1") (pin "41") (pinfunction "GPIO45_41") (pintype "passive"))
    )
    (net (code "55") (name "/GPIO46") (class "Default")
      (node (ref "J2") (pin "4") (pinfunction "4_4") (pintype "passive"))
      (node (ref "U1") (pin "44") (pinfunction "GPIO46_44") (pintype "passive"))
    )
    (net (code "56") (name "/GPIO47") (class "Default")
      (node (ref "J2") (pin "23") (pinfunction "23_23") (pintype "passive"))
      (node (ref "U1") (pin "27") (pinfunction "GPIO47/SPICLK_P_DIFF/SUBSPICLK_P_DIFF_27") (pintype "passive"))
    )
    (net (code "57") (name "/GPIO48") (class "Default")
      (node (ref "J2") (pin "22") (pinfunction "22_22") (pintype "passive"))
      (node (ref "U1") (pin "30") (pinfunction "GPIO48/SPICLK_N_DIFF/SUBSPICLK_N_DIFF_30") (pintype "passive"))
    )
    (net (code "58") (name "/RTS_FTDI") (class "Default")
      (node (ref "Q1") (pin "2") (pinfunction "E_2") (pintype "passive"))
      (node (ref "R18") (pin "1") (pinfunction "1_1") (pintype "passive"))
      (node (ref "U2") (pin "19") (pinfunction "~{RTS}_19") (pintype "passive"))
    )
    (net (code "59") (name "/RXD_FTDI") (class "Default")
      (node (ref "R19") (pin "2") (pinfunction "2_2") (pintype "passive"))
      (node (ref "U2") (pin "1") (pinfunction "RXD_1") (pintype "passive"))
    )
    (net (code "60") (name "/TXD_FTDI") (class "Default")
      (node (ref "R20") (pin "2") (pinfunction "2_2") (pintype "passive"))
      (node (ref "U2") (pin "17") (pinfunction "TXD_17") (pintype "passive"))
    )
    (net (code "61") (name "/U0RXD") (class "Default")
      (node (ref "J2") (pin "6") (pinfunction "6_6") (pintype "passive"))
      (node (ref "R20") (pin "1") (pinfunction "1_1") (pintype "passive"))
      (node (ref "U1") (pin "40") (pinfunction "U0RXD/GPIO44/CLK_OUT2_40") (pintype "passive"))
    )
    (net (code "62") (name "/U0TXD") (class "Default")
      (node (ref "J2") (pin "7") (pinfunction "7_7") (pintype "passive"))
      (node (ref "R19") (pin "1") (pinfunction "1_1") (pintype "passive"))
      (node (ref "U1") (pin "39") (pinfunction "U0TXD/GPIO43/CLK_OUT1_39") (pintype "passive"))
    )
    (net (code "63") (name "/VBUS_SENSE") (class "Default")
      (node (ref "R10") (pin "1") (pinfunction "1_1") (pintype "passive"))
      (node (ref "R13") (pin "1") (pinfunction "1_1") (pintype "passive"))
      (node (ref "U2") (pin "16") (pinfunction "CBUS3_16") (pintype "passive"))
    )
    (net (code "64") (name "GND") (class "Default")
      (node (ref "C1") (pin "1") (pinfunction "1_1") (pintype "passive"))
      (node (ref "C10") (pin "1") (pinfunction "1_1") (pintype "passive"))
      (node (ref "C11") (pin "1") (pinfunction "1_1") (pintype "passive"))
      (node (ref "C12") (pin "1") (pinfunction "1_1") (pintype "passive"))
      (node (ref "C13") (pin "1") (pinfunction "1_1") (pintype "passive"))
      (node (ref "C14") (pin "1") (pinfunction "1_1") (pintype "passive"))
      (node (ref "C15") (pin "1") (pinfunction "1_1") (pintype "passive"))
      (node (ref "C16") (pin "1") (pinfunction "1_1") (pintype "passive"))
      (node (ref "C17") (pin "1") (pinfunction "1_1") (pintype "passive"))
      (node (ref "C2") (pin "1") (pinfunction "1_1") (pintype "passive"))
      (node (ref "C3") (pin "1") (pinfunction "1_1") (pintype "passive"))
      (node (ref "C4") (pin "1") (pinfunction "1_1") (pintype "passive"))
      (node (ref "C5") (pin "1") (pinfunction "1_1") (pintype "passive"))
      (node (ref "C6") (pin "1") (pinfunction "1_1") (pintype "passive"))
      (node (ref "C7") (pin "1") (pinfunction "1_1") (pintype "passive"))
      (node (ref "C8") (pin "1") (pinfunction "1_1") (pintype "passive"))
      (node (ref "C9") (pin "1") (pinfunction "1_1") (pintype "passive"))
      (node (ref "D1") (pin "1") (pinfunction "1_1") (pintype "passive"))
      (node (ref "D3") (pin "1") (pinfunction "1_1") (pintype "passive"))
      (node (ref "D4") (pin "1") (pinfunction "1_1") (pintype "passive"))
      (node (ref "D5") (pin "1") (pinfunction "1_1") (pintype "passive"))
      (node (ref "D6") (pin "1") (pinfunction "1_1") (pintype "passive"))
      (node (ref "D7") (pin "1") (pinfunction "1_1") (pintype "passive"))
      (node (ref "D8") (pin "1") (pinfunction "1_1") (pintype "passive"))
      (node (ref "J1") (pin "1") (pinfunction "1_1") (pintype "passive"))
      (node (ref "J1") (pin "23") (pinfunction "23_23") (pintype "passive"))
      (node (ref "J2") (pin "2") (pinfunction "2_2") (pintype "passive"))
      (node (ref "J2") (pin "24") (pinfunction "24_24") (pintype "passive"))
      (node (ref "J3") (pin "A1B12") (pinfunction "GND_A1B12_A1B12") (pintype "passive"))
      (node (ref "J3") (pin "B1A12") (pinfunction "GND_B1A12_B1A12") (pintype "passive"))
      (node (ref "J3") (pin "S1") (pinfunction "SHIELD_1_S1") (pintype "passive"))
      (node (ref "J3") (pin "S2") (pinfunction "SHIELD_2_S2") (pintype "passive"))
      (node (ref "J3") (pin "S3") (pinfunction "SHIELD_3_S3") (pintype "passive"))
      (node (ref "J3") (pin "S4") (pinfunction "SHIELD_4_S4") (pintype "passive"))
      (node (ref "J4") (pin "A1B12") (pinfunction "GND_A1B12_A1B12") (pintype "passive"))
      (node (ref "J4") (pin "B1A12") (pinfunction "GND_B1A12_B1A12") (pintype "passive"))
      (node (ref "J4") (pin "S1") (pinfunction "SHIELD_1_S1") (pintype "passive"))
      (node (ref "J4") (pin "S2") (pinfunction "SHIELD_2_S2") (pintype "passive"))
      (node (ref "J4") (pin "S3") (pinfunction "SHIELD_3_S3") (pintype "passive"))
      (node (ref "J4") (pin "S4") (pinfunction "SHIELD_4_S4") (pintype "passive"))
      (node (ref "R11") (pin "1") (pinfunction "1_1") (pintype "passive"))
      (node (ref "R12") (pin "1") (pinfunction "1_1") (pintype "passive"))
      (node (ref "R13") (pin "2") (pinfunction "2_2") (pintype "passive"))
      (node (ref "R14") (pin "1") (pinfunction "1_1") (pintype "passive"))
      (node (ref "R15") (pin "1") (pinfunction "1_1") (pintype "passive"))
      (node (ref "R9") (pin "2") (pinfunction "2_2") (pintype "passive"))
      (node (ref "SW1") (pin "3") (pinfunction "3_3") (pintype "passive"))
      (node (ref "SW1") (pin "4") (pinfunction "4_4") (pintype "passive"))
      (node (ref "SW2") (pin "3") (pinfunction "3_3") (pintype "passive"))
      (node (ref "SW2") (pin "4") (pinfunction "4_4") (pintype "passive"))
      (node (ref "U1") (pin "1") (pinfunction "GND_01_1") (pintype "passive"))
      (node (ref "U1") (pin "2") (pinfunction "GND_02_2") (pintype "passive"))
      (node (ref "U1") (pin "42") (pinfunction "GND_42") (pintype "passive"))
      (node (ref "U1") (pin "43") (pinfunction "GND_43") (pintype "passive"))
      (node (ref "U1") (pin "46") (pinfunction "GND_46_46") (pintype "passive"))
      (node (ref "U1") (pin "47") (pinfunction "GND_47_47") (pintype "passive"))
      (node (ref "U1") (pin "48") (pinfunction "GND_48_48") (pintype "passive"))
      (node (ref "U1") (pin "49") (pinfunction "GND_49_49") (pintype "passive"))
      (node (ref "U1") (pin "50") (pinfunction "GND_50_50") (pintype "passive"))
      (node (ref "U1") (pin "51") (pinfunction "GND_51_51") (pintype "passive"))
      (node (ref "U1") (pin "52") (pinfunction "GND_52_52") (pintype "passive"))
      (node (ref "U1") (pin "53") (pinfunction "GND_53_53") (pintype "passive"))
      (node (ref "U1") (pin "54") (pinfunction "GND_54_54") (pintype "passive"))
      (node (ref "U1") (pin "55") (pinfunction "GND_55_55") (pintype "passive"))
      (node (ref "U1") (pin "56") (pinfunction "GND_56_56") (pintype "passive"))
      (node (ref "U1") (pin "57") (pinfunction "GND_57_57") (pintype "passive"))
      (node (ref "U1") (pin "58") (pinfunction "GND_58_58") (pintype "passive"))
      (node (ref "U1") (pin "59") (pinfunction "GND_59_59") (pintype "passive"))
      (node (ref "U1") (pin "60") (pinfunction "GND_60_60") (pintype "passive"))
      (node (ref "U1") (pin "61") (pinfunction "GND_61_61") (pintype "passive"))
      (node (ref "U1") (pin "62") (pinfunction "GND_62_62") (pintype "passive"))
      (node (ref "U1") (pin "63") (pinfunction "GND_63_63") (pintype "passive"))
      (node (ref "U1") (pin "64") (pinfunction "GND_64_64") (pintype "passive"))
      (node (ref "U1") (pin "65") (pinfunction "GND_65_65") (pintype "passive"))
      (node (ref "U1") (pin "66") (pinfunction "GND_66_66") (pintype "passive"))
      (node (ref "U1") (pin "67") (pinfunction "GND_67_67") (pintype "passive"))
      (node (ref "U1") (pin "68") (pinfunction "GND_68_68") (pintype "passive"))
      (node (ref "U1") (pin "69") (pinfunction "GND_69_69") (pintype "passive"))
      (node (ref "U1") (pin "70") (pinfunction "GND_70_70") (pintype "passive"))
      (node (ref "U1") (pin "71") (pinfunction "GND_71_71") (pintype "passive"))
      (node (ref "U1") (pin "72") (pinfunction "GND_72_72") (pintype "passive"))
      (node (ref "U1") (pin "73") (pinfunction "GND_73_73") (pintype "passive"))
      (node (ref "U2") (pin "13") (pinfunction "GND_13") (pintype "passive"))
      (node (ref "U2") (pin "21") (pinfunction "GND_21") (pintype "passive"))
      (node (ref "U2") (pin "3") (pinfunction "GND_3") (pintype "passive"))
      (node (ref "U3") (pin "2") (pinfunction "GND_2") (pintype "power_in"))
      (node (ref "U3") (pin "4") (pinfunction "GND_4") (pintype "power_in"))
    )
    (net (code "65") (name "Net-(D1-Pad2)") (class "Default")
      (node (ref "D1") (pin "2") (pinfunction "2_2") (pintype "passive"))
      (node (ref "R3") (pin "1") (pinfunction "1_1") (pintype "passive"))
    )
    (net (code "66") (name "Net-(D2-Pad2)") (class "Default")
      (node (ref "D2") (pin "2") (pinfunction "2_2") (pintype "passive"))
      (node (ref "R4") (pin "1") (pinfunction "1_1") (pintype "passive"))
    )
    (net (code "67") (name "Net-(J3-CC1)") (class "Default")
      (node (ref "J3") (pin "A5") (pinfunction "CC1_A5") (pintype "passive"))
      (node (ref "R12") (pin "2") (pinfunction "2_2") (pintype "passive"))
    )
    (net (code "68") (name "Net-(J3-CC2)") (class "Default")
      (node (ref "J3") (pin "B5") (pinfunction "CC2_B5") (pintype "passive"))
      (node (ref "R11") (pin "2") (pinfunction "2_2") (pintype "passive"))
    )
    (net (code "69") (name "Net-(J4-CC1)") (class "Default")
      (node (ref "J4") (pin "A5") (pinfunction "CC1_A5") (pintype "passive"))
      (node (ref "R15") (pin "2") (pinfunction "2_2") (pintype "passive"))
    )
    (net (code "70") (name "Net-(J4-CC2)") (class "Default")
      (node (ref "J4") (pin "B5") (pinfunction "CC2_B5") (pintype "passive"))
      (node (ref "R14") (pin "2") (pinfunction "2_2") (pintype "passive"))
    )
    (net (code "71") (name "Net-(Q1-B)") (class "Default")
      (node (ref "Q1") (pin "1") (pinfunction "B_1") (pintype "passive"))
      (node (ref "R16") (pin "2") (pinfunction "2_2") (pintype "passive"))
    )
    (net (code "72") (name "Net-(Q2-B)") (class "Default")
      (node (ref "Q2") (pin "1") (pinfunction "B_1") (pintype "passive"))
      (node (ref "R18") (pin "2") (pinfunction "2_2") (pintype "passive"))
    )
    (net (code "73") (name "Net-(U2-CBUS0)") (class "Default")
      (node (ref "R9") (pin "1") (pinfunction "1_1") (pintype "passive"))
      (node (ref "U2") (pin "15") (pinfunction "CBUS0_15") (pintype "passive"))
    )
    (net (code "74") (name "unconnected-(J1-Pad24)") (class "Default")
      (node (ref "J1") (pin "24") (pinfunction "24_24") (pintype "passive+no_connect"))
    )
    (net (code "75") (name "unconnected-(J3-SBU1-PadA8)") (class "Default")
      (node (ref "J3") (pin "A8") (pinfunction "SBU1_A8") (pintype "passive+no_connect"))
    )
    (net (code "76") (name "unconnected-(J3-SBU2-PadB8)") (class "Default")
      (node (ref "J3") (pin "B8") (pinfunction "SBU2_B8") (pintype "passive+no_connect"))
    )
    (net (code "77") (name "unconnected-(J4-SBU1-PadA8)") (class "Default")
      (node (ref "J4") (pin "A8") (pinfunction "SBU1_A8") (pintype "passive+no_connect"))
    )
    (net (code "78") (name "unconnected-(J4-SBU2-PadB8)") (class "Default")
      (node (ref "J4") (pin "B8") (pinfunction "SBU2_B8") (pintype "passive+no_connect"))
    )
    (net (code "79") (name "unconnected-(U2-CBUS1-Pad14)") (class "Default")
      (node (ref "U2") (pin "14") (pinfunction "CBUS1_14") (pintype "passive+no_connect"))
    )
    (net (code "80") (name "unconnected-(U2-CBUS2-Pad7)") (class "Default")
      (node (ref "U2") (pin "7") (pinfunction "CBUS2_7") (pintype "passive+no_connect"))
    )
    (net (code "81") (name "unconnected-(U2-~{CTS}-Pad6)") (class "Default")
      (node (ref "U2") (pin "6") (pinfunction "~{CTS}_6") (pintype "passive+no_connect"))
    )
    (net (code "82") (name "unconnected-(U2-~{DCD}-Pad5)") (class "Default")
      (node (ref "U2") (pin "5") (pinfunction "~{DCD}_5") (pintype "passive+no_connect"))
    )
    (net (code "83") (name "unconnected-(U2-~{DSR}-Pad4)") (class "Default")
      (node (ref "U2") (pin "4") (pinfunction "~{DSR}_4") (pintype "passive+no_connect"))
    )
    (net (code "84") (name "unconnected-(U2-~{RI}-Pad2)") (class "Default")
      (node (ref "U2") (pin "2") (pinfunction "~{RI}_2") (pintype "passive+no_connect"))
    )
  )
)
